# STEPPER.net
KiCad netlist of a schematic drawn in Altium Designer
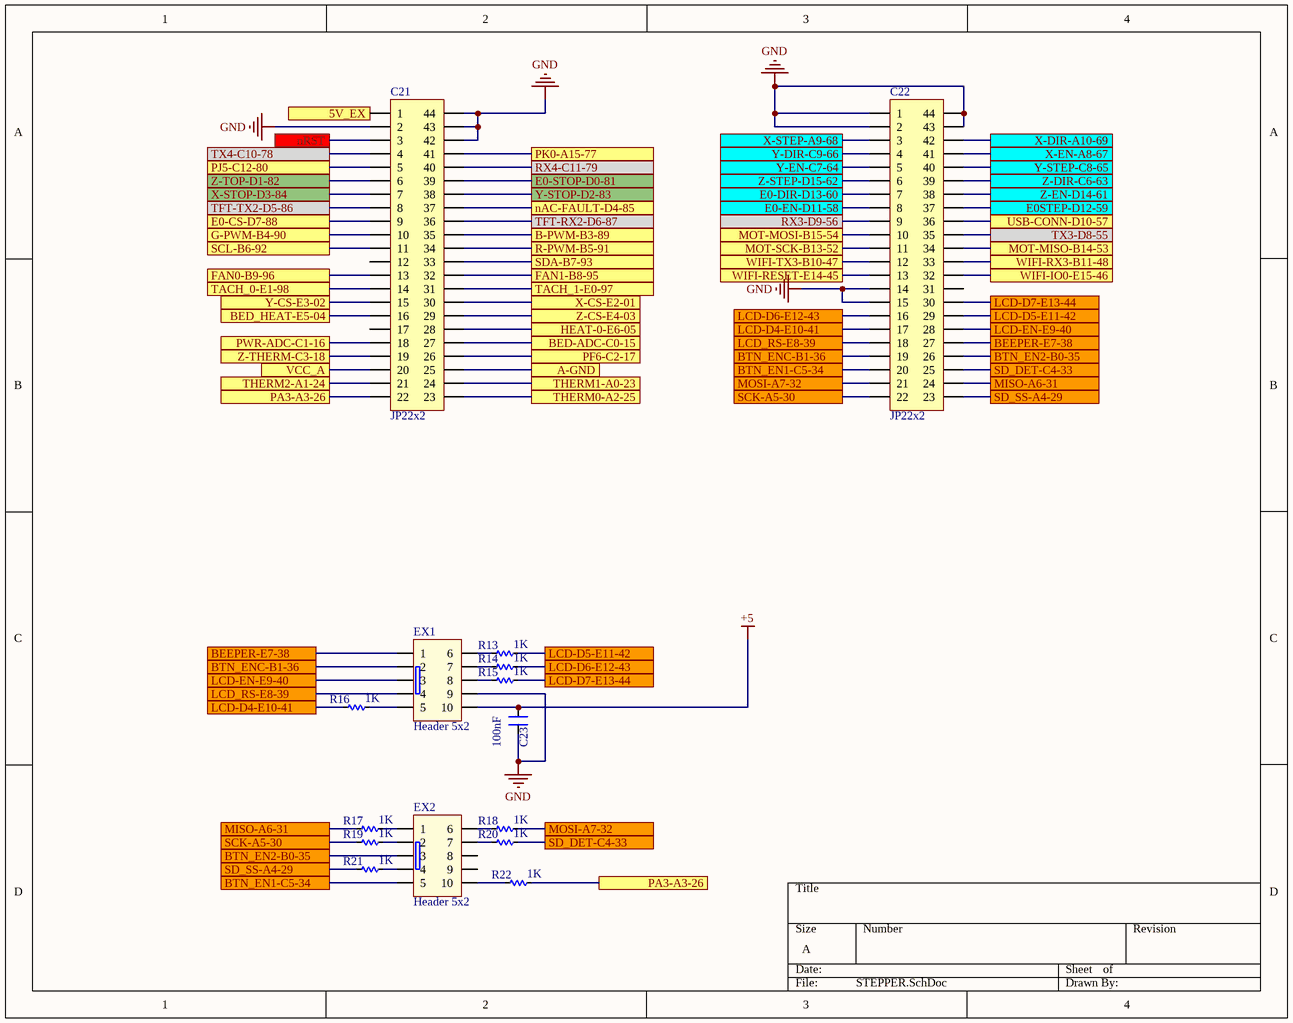
[diagram p0: STEPPER.SchDoc]

(export (version "E")
  (design (tool "Eeschema 10.0.6"))
  (components
    (comp (ref "C21")
      (value "JP22x2")
      (footprint "JP22-C2T")
      (description "WR-PHD 2.54 mm Dual Socket Header")
      (fields
        (field (name "MANUFACTURER") "Würth Elektronik eiSos GmbH")
        (field (name "PARTNO") "61304421821")
        (field (name "CREATED BY") "Karrer Zheng")
      )
      (libsource (lib "nhan") (part "JP22x2"))
    )
    (comp (ref "C22")
      (value "JP22x2")
      (footprint "JP22-C2T")
      (description "WR-PHD 2.54 mm Dual Socket Header")
      (fields
        (field (name "MANUFACTURER") "Würth Elektronik eiSos GmbH")
        (field (name "PARTNO") "61304421821")
        (field (name "CREATED BY") "Karrer Zheng")
      )
      (libsource (lib "nhan") (part "JP22x2"))
    )
    (comp (ref "C23") (value "100nF") (footprint "CN-SMD-0603_big") (libsource (lib "nhan") (part "CN")))
    (comp (ref "EX1")
      (value "Header 5x2")
      (footprint "Hed2X5")
      (libsource (lib "syhaunguyen") (part "HED5x2"))
    )
    (comp (ref "EX2")
      (value "Header 5x2")
      (footprint "Hed2X5")
      (libsource (lib "syhaunguyen") (part "HED5x2"))
    )
    (comp (ref "R13") (value "1K") (footprint "RES-SMD-0603_BIG") (libsource (lib "nhan") (part "R")))
    (comp (ref "R14") (value "1K") (footprint "RES-SMD-0603_BIG") (libsource (lib "nhan") (part "R")))
    (comp (ref "R15") (value "1K") (footprint "RES-SMD-0603_BIG") (libsource (lib "nhan") (part "R")))
    (comp (ref "R16") (value "1K") (footprint "RES-SMD-0603_BIG") (libsource (lib "nhan") (part "R")))
    (comp (ref "R17") (value "1K") (footprint "RES-SMD-0603_BIG") (libsource (lib "nhan") (part "R")))
    (comp (ref "R18") (value "1K") (footprint "RES-SMD-0603_BIG") (libsource (lib "nhan") (part "R")))
    (comp (ref "R19") (value "1K") (footprint "RES-SMD-0603_BIG") (libsource (lib "nhan") (part "R")))
    (comp (ref "R20") (value "1K") (footprint "RES-SMD-0603_BIG") (libsource (lib "nhan") (part "R")))
    (comp (ref "R21") (value "1K") (footprint "RES-SMD-0603_BIG") (libsource (lib "nhan") (part "R")))
    (comp (ref "R22") (value "1K") (footprint "RES-SMD-0603_BIG") (libsource (lib "nhan") (part "R")))
  )
  (nets
    (net (code "1") (name "+5") (class "Default")
      (node (ref "C23") (pin "2") (pinfunction "2_2") (pintype "passive"))
      (node (ref "EX1") (pin "10") (pinfunction "10_10") (pintype "passive"))
    )
    (net (code "2") (name "/5V_EX") (class "Default")
      (node (ref "C21") (pin "1") (pinfunction "1_1") (pintype "passive"))
    )
    (net (code "3") (name "/A-GND") (class "Default")
      (node (ref "C21") (pin "25") (pinfunction "25_25") (pintype "passive"))
    )
    (net (code "4") (name "/B-PWM-B3-89") (class "Default")
      (node (ref "C21") (pin "35") (pinfunction "35_35") (pintype "passive"))
    )
    (net (code "5") (name "/BED-ADC-C0-15") (class "Default")
      (node (ref "C21") (pin "27") (pinfunction "27_27") (pintype "passive"))
    )
    (net (code "6") (name "/BED_HEAT-E5-04") (class "Default")
      (node (ref "C21") (pin "16") (pinfunction "16_16") (pintype "passive"))
    )
    (net (code "7") (name "/BEEPER-E7-38") (class "Default")
      (node (ref "C22") (pin "27") (pinfunction "27_27") (pintype "passive"))
      (node (ref "EX1") (pin "1") (pinfunction "1_1") (pintype "passive"))
    )
    (net (code "8") (name "/BTN_EN1-C5-34") (class "Default")
      (node (ref "C22") (pin "20") (pinfunction "20_20") (pintype "passive"))
      (node (ref "EX2") (pin "5") (pinfunction "5_5") (pintype "passive"))
    )
    (net (code "9") (name "/BTN_EN2-B0-35") (class "Default")
      (node (ref "C22") (pin "26") (pinfunction "26_26") (pintype "passive"))
      (node (ref "EX2") (pin "3") (pinfunction "3_3") (pintype "passive"))
    )
    (net (code "10") (name "/BTN_ENC-B1-36") (class "Default")
      (node (ref "C22") (pin "19") (pinfunction "19_19") (pintype "passive"))
      (node (ref "EX1") (pin "2") (pinfunction "2_2") (pintype "passive"))
    )
    (net (code "11") (name "/E0-CS-D7-88") (class "Default")
      (node (ref "C21") (pin "9") (pinfunction "9_9") (pintype "passive"))
    )
    (net (code "12") (name "/E0-DIR-D13-60") (class "Default")
      (node (ref "C22") (pin "7") (pinfunction "7_7") (pintype "passive"))
    )
    (net (code "13") (name "/E0-EN-D11-58") (class "Default")
      (node (ref "C22") (pin "8") (pinfunction "8_8") (pintype "passive"))
    )
    (net (code "14") (name "/E0-STOP-D0-81") (class "Default")
      (node (ref "C21") (pin "39") (pinfunction "39_39") (pintype "passive"))
    )
    (net (code "15") (name "/E0STEP-D12-59") (class "Default")
      (node (ref "C22") (pin "37") (pinfunction "37_37") (pintype "passive"))
    )
    (net (code "16") (name "/FAN0-B9-96") (class "Default")
      (node (ref "C21") (pin "13") (pinfunction "13_13") (pintype "passive"))
    )
    (net (code "17") (name "/FAN1-B8-95") (class "Default")
      (node (ref "C21") (pin "32") (pinfunction "32_32") (pintype "passive"))
    )
    (net (code "18") (name "/G-PWM-B4-90") (class "Default")
      (node (ref "C21") (pin "10") (pinfunction "10_10") (pintype "passive"))
    )
    (net (code "19") (name "/HEAT-0-E6-05") (class "Default")
      (node (ref "C21") (pin "28") (pinfunction "28_28") (pintype "passive"))
    )
    (net (code "20") (name "/LCD-D4-E10-41") (class "Default")
      (node (ref "C22") (pin "17") (pinfunction "17_17") (pintype "passive"))
      (node (ref "R16") (pin "2") (pinfunction "2_2") (pintype "passive"))
    )
    (net (code "21") (name "/LCD-D5-E11-42") (class "Default")
      (node (ref "C22") (pin "29") (pinfunction "29_29") (pintype "passive"))
      (node (ref "R13") (pin "1") (pinfunction "1_1") (pintype "passive"))
    )
    (net (code "22") (name "/LCD-D6-E12-43") (class "Default")
      (node (ref "C22") (pin "16") (pinfunction "16_16") (pintype "passive"))
      (node (ref "R14") (pin "1") (pinfunction "1_1") (pintype "passive"))
    )
    (net (code "23") (name "/LCD-D7-E13-44") (class "Default")
      (node (ref "C22") (pin "30") (pinfunction "30_30") (pintype "passive"))
      (node (ref "R15") (pin "1") (pinfunction "1_1") (pintype "passive"))
    )
    (net (code "24") (name "/LCD-EN-E9-40") (class "Default")
      (node (ref "C22") (pin "28") (pinfunction "28_28") (pintype "passive"))
      (node (ref "EX1") (pin "3") (pinfunction "3_3") (pintype "passive"))
    )
    (net (code "25") (name "/LCD_RS-E8-39") (class "Default")
      (node (ref "C22") (pin "18") (pinfunction "18_18") (pintype "passive"))
      (node (ref "EX1") (pin "4") (pinfunction "4_4") (pintype "passive"))
    )
    (net (code "26") (name "/MISO-A6-31") (class "Default")
      (node (ref "C22") (pin "24") (pinfunction "24_24") (pintype "passive"))
      (node (ref "R17") (pin "2") (pinfunction "2_2") (pintype "passive"))
    )
    (net (code "27") (name "/MOSI-A7-32") (class "Default")
      (node (ref "C22") (pin "21") (pinfunction "21_21") (pintype "passive"))
      (node (ref "R18") (pin "1") (pinfunction "1_1") (pintype "passive"))
    )
    (net (code "28") (name "/MOT-MISO-B14-53") (class "Default")
      (node (ref "C22") (pin "34") (pinfunction "34_34") (pintype "passive"))
    )
    (net (code "29") (name "/MOT-MOSI-B15-54") (class "Default")
      (node (ref "C22") (pin "10") (pinfunction "10_10") (pintype "passive"))
    )
    (net (code "30") (name "/MOT-SCK-B13-52") (class "Default")
      (node (ref "C22") (pin "11") (pinfunction "11_11") (pintype "passive"))
    )
    (net (code "31") (name "/PA3-A3-26") (class "Default")
      (node (ref "C21") (pin "22") (pinfunction "22_22") (pintype "passive"))
      (node (ref "R22") (pin "1") (pinfunction "1_1") (pintype "passive"))
    )
    (net (code "32") (name "/PF6-C2-17") (class "Default")
      (node (ref "C21") (pin "26") (pinfunction "26_26") (pintype "passive"))
    )
    (net (code "33") (name "/PJ5-C12-80") (class "Default")
      (node (ref "C21") (pin "5") (pinfunction "5_5") (pintype "passive"))
    )
    (net (code "34") (name "/PK0-A15-77") (class "Default")
      (node (ref "C21") (pin "41") (pinfunction "41_41") (pintype "passive"))
    )
    (net (code "35") (name "/PWR-ADC-C1-16") (class "Default")
      (node (ref "C21") (pin "18") (pinfunction "18_18") (pintype "passive"))
    )
    (net (code "36") (name "/R-PWM-B5-91") (class "Default")
      (node (ref "C21") (pin "34") (pinfunction "34_34") (pintype "passive"))
    )
    (net (code "37") (name "/RX3-D9-56") (class "Default")
      (node (ref "C22") (pin "9") (pinfunction "9_9") (pintype "passive"))
    )
    (net (code "38") (name "/RX4-C11-79") (class "Default")
      (node (ref "C21") (pin "40") (pinfunction "40_40") (pintype "passive"))
    )
    (net (code "39") (name "/SCK-A5-30") (class "Default")
      (node (ref "C22") (pin "22") (pinfunction "22_22") (pintype "passive"))
      (node (ref "R19") (pin "2") (pinfunction "2_2") (pintype "passive"))
    )
    (net (code "40") (name "/SCL-B6-92") (class "Default")
      (node (ref "C21") (pin "11") (pinfunction "11_11") (pintype "passive"))
    )
    (net (code "41") (name "/SDA-B7-93") (class "Default")
      (node (ref "C21") (pin "33") (pinfunction "33_33") (pintype "passive"))
    )
    (net (code "42") (name "/SD_DET-C4-33") (class "Default")
      (node (ref "C22") (pin "25") (pinfunction "25_25") (pintype "passive"))
      (node (ref "R20") (pin "1") (pinfunction "1_1") (pintype "passive"))
    )
    (net (code "43") (name "/SD_SS-A4-29") (class "Default")
      (node (ref "C22") (pin "23") (pinfunction "23_23") (pintype "passive"))
      (node (ref "R21") (pin "2") (pinfunction "2_2") (pintype "passive"))
    )
    (net (code "44") (name "/TACH_0-E1-98") (class "Default")
      (node (ref "C21") (pin "14") (pinfunction "14_14") (pintype "passive"))
    )
    (net (code "45") (name "/TACH_1-E0-97") (class "Default")
      (node (ref "C21") (pin "31") (pinfunction "31_31") (pintype "passive"))
    )
    (net (code "46") (name "/TFT-RX2-D6-87") (class "Default")
      (node (ref "C21") (pin "36") (pinfunction "36_36") (pintype "passive"))
    )
    (net (code "47") (name "/TFT-TX2-D5-86") (class "Default")
      (node (ref "C21") (pin "8") (pinfunction "8_8") (pintype "passive"))
    )
    (net (code "48") (name "/THERM0-A2-25") (class "Default")
      (node (ref "C21") (pin "23") (pinfunction "23_23") (pintype "passive"))
    )
    (net (code "49") (name "/THERM1-A0-23") (class "Default")
      (node (ref "C21") (pin "24") (pinfunction "24_24") (pintype "passive"))
    )
    (net (code "50") (name "/THERM2-A1-24") (class "Default")
      (node (ref "C21") (pin "21") (pinfunction "21_21") (pintype "passive"))
    )
    (net (code "51") (name "/TX3-D8-55") (class "Default")
      (node (ref "C22") (pin "35") (pinfunction "35_35") (pintype "passive"))
    )
    (net (code "52") (name "/TX4-C10-78") (class "Default")
      (node (ref "C21") (pin "4") (pinfunction "4_4") (pintype "passive"))
    )
    (net (code "53") (name "/USB-CONN-D10-57") (class "Default")
      (node (ref "C22") (pin "36") (pinfunction "36_36") (pintype "passive"))
    )
    (net (code "54") (name "/VCC_A") (class "Default")
      (node (ref "C21") (pin "20") (pinfunction "20_20") (pintype "passive"))
    )
    (net (code "55") (name "/WIFI-IO0-E15-46") (class "Default")
      (node (ref "C22") (pin "32") (pinfunction "32_32") (pintype "passive"))
    )
    (net (code "56") (name "/WIFI-RESET-E14-45") (class "Default")
      (node (ref "C22") (pin "13") (pinfunction "13_13") (pintype "passive"))
    )
    (net (code "57") (name "/WIFI-RX3-B11-48") (class "Default")
      (node (ref "C22") (pin "33") (pinfunction "33_33") (pintype "passive"))
    )
    (net (code "58") (name "/WIFI-TX3-B10-47") (class "Default")
      (node (ref "C22") (pin "12") (pinfunction "12_12") (pintype "passive"))
    )
    (net (code "59") (name "/X-CS-E2-01") (class "Default")
      (node (ref "C21") (pin "30") (pinfunction "30_30") (pintype "passive"))
    )
    (net (code "60") (name "/X-DIR-A10-69") (class "Default")
      (node (ref "C22") (pin "42") (pinfunction "42_42") (pintype "passive"))
    )
    (net (code "61") (name "/X-EN-A8-67") (class "Default")
      (node (ref "C22") (pin "41") (pinfunction "41_41") (pintype "passive"))
    )
    (net (code "62") (name "/X-STEP-A9-68") (class "Default")
      (node (ref "C22") (pin "3") (pinfunction "3_3") (pintype "passive"))
    )
    (net (code "63") (name "/X-STOP-D3-84") (class "Default")
      (node (ref "C21") (pin "7") (pinfunction "7_7") (pintype "passive"))
    )
    (net (code "64") (name "/Y-CS-E3-02") (class "Default")
      (node (ref "C21") (pin "15") (pinfunction "15_15") (pintype "passive"))
    )
    (net (code "65") (name "/Y-DIR-C9-66") (class "Default")
      (node (ref "C22") (pin "4") (pinfunction "4_4") (pintype "passive"))
    )
    (net (code "66") (name "/Y-EN-C7-64") (class "Default")
      (node (ref "C22") (pin "5") (pinfunction "5_5") (pintype "passive"))
    )
    (net (code "67") (name "/Y-STEP-C8-65") (class "Default")
      (node (ref "C22") (pin "40") (pinfunction "40_40") (pintype "passive"))
    )
    (net (code "68") (name "/Y-STOP-D2-83") (class "Default")
      (node (ref "C21") (pin "38") (pinfunction "38_38") (pintype "passive"))
    )
    (net (code "69") (name "/Z-CS-E4-03") (class "Default")
      (node (ref "C21") (pin "29") (pinfunction "29_29") (pintype "passive"))
    )
    (net (code "70") (name "/Z-DIR-C6-63") (class "Default")
      (node (ref "C22") (pin "39") (pinfunction "39_39") (pintype "passive"))
    )
    (net (code "71") (name "/Z-EN-D14-61") (class "Default")
      (node (ref "C22") (pin "38") (pinfunction "38_38") (pintype "passive"))
    )
    (net (code "72") (name "/Z-STEP-D15-62") (class "Default")
      (node (ref "C22") (pin "6") (pinfunction "6_6") (pintype "passive"))
    )
    (net (code "73") (name "/Z-THERM-C3-18") (class "Default")
      (node (ref "C21") (pin "19") (pinfunction "19_19") (pintype "passive"))
    )
    (net (code "74") (name "/Z-TOP-D1-82") (class "Default")
      (node (ref "C21") (pin "6") (pinfunction "6_6") (pintype "passive"))
    )
    (net (code "75") (name "/nAC-FAULT-D4-85") (class "Default")
      (node (ref "C21") (pin "37") (pinfunction "37_37") (pintype "passive"))
    )
    (net (code "76") (name "/nRST") (class "Default")
      (node (ref "C21") (pin "3") (pinfunction "3_3") (pintype "passive"))
    )
    (net (code "77") (name "GND") (class "Default")
      (node (ref "C21") (pin "2") (pinfunction "2_2") (pintype "passive"))
      (node (ref "C21") (pin "42") (pinfunction "42_42") (pintype "passive"))
      (node (ref "C21") (pin "43") (pinfunction "43_43") (pintype "passive"))
      (node (ref "C21") (pin "44") (pinfunction "44_44") (pintype "passive"))
      (node (ref "C22") (pin "1") (pinfunction "1_1") (pintype "passive"))
      (node (ref "C22") (pin "14") (pinfunction "14_14") (pintype "passive"))
      (node (ref "C22") (pin "15") (pinfunction "15_15") (pintype "passive"))
      (node (ref "C22") (pin "2") (pinfunction "2_2") (pintype "passive"))
      (node (ref "C22") (pin "43") (pinfunction "43_43") (pintype "passive"))
      (node (ref "C22") (pin "44") (pinfunction "44_44") (pintype "passive"))
      (node (ref "C23") (pin "1") (pinfunction "1_1") (pintype "passive"))
      (node (ref "EX1") (pin "9") (pinfunction "9_9") (pintype "passive"))
    )
    (net (code "78") (name "Net-(EX1-Pad5)") (class "Default")
      (node (ref "EX1") (pin "5") (pinfunction "5_5") (pintype "passive"))
      (node (ref "R16") (pin "1") (pinfunction "1_1") (pintype "passive"))
    )
    (net (code "79") (name "Net-(EX1-Pad6)") (class "Default")
      (node (ref "EX1") (pin "6") (pinfunction "6_6") (pintype "passive"))
      (node (ref "R13") (pin "2") (pinfunction "2_2") (pintype "passive"))
    )
    (net (code "80") (name "Net-(EX1-Pad7)") (class "Default")
      (node (ref "EX1") (pin "7") (pinfunction "7_7") (pintype "passive"))
      (node (ref "R14") (pin "2") (pinfunction "2_2") (pintype "passive"))
    )
    (net (code "81") (name "Net-(EX1-Pad8)") (class "Default")
      (node (ref "EX1") (pin "8") (pinfunction "8_8") (pintype "passive"))
      (node (ref "R15") (pin "2") (pinfunction "2_2") (pintype "passive"))
    )
    (net (code "82") (name "Net-(EX2-Pad1)") (class "Default")
      (node (ref "EX2") (pin "1") (pinfunction "1_1") (pintype "passive"))
      (node (ref "R17") (pin "1") (pinfunction "1_1") (pintype "passive"))
    )
    (net (code "83") (name "Net-(EX2-Pad2)") (class "Default")
      (node (ref "EX2") (pin "2") (pinfunction "2_2") (pintype "passive"))
      (node (ref "R19") (pin "1") (pinfunction "1_1") (pintype "passive"))
    )
    (net (code "84") (name "Net-(EX2-Pad4)") (class "Default")
      (node (ref "EX2") (pin "4") (pinfunction "4_4") (pintype "passive"))
      (node (ref "R21") (pin "1") (pinfunction "1_1") (pintype "passive"))
    )
    (net (code "85") (name "Net-(EX2-Pad6)") (class "Default")
      (node (ref "EX2") (pin "6") (pinfunction "6_6") (pintype "passive"))
      (node (ref "R18") (pin "2") (pinfunction "2_2") (pintype "passive"))
    )
    (net (code "86") (name "Net-(EX2-Pad7)") (class "Default")
      (node (ref "EX2") (pin "7") (pinfunction "7_7") (pintype "passive"))
      (node (ref "R20") (pin "2") (pinfunction "2_2") (pintype "passive"))
    )
    (net (code "87") (name "Net-(EX2-Pad10)") (class "Default")
      (node (ref "EX2") (pin "10") (pinfunction "10_10") (pintype "passive"))
      (node (ref "R22") (pin "2") (pinfunction "2_2") (pintype "passive"))
    )
    (net (code "88") (name "unconnected-(C21-Pad12)") (class "Default")
      (node (ref "C21") (pin "12") (pinfunction "12_12") (pintype "passive"))
    )
    (net (code "89") (name "unconnected-(C21-Pad17)") (class "Default")
      (node (ref "C21") (pin "17") (pinfunction "17_17") (pintype "passive"))
    )
    (net (code "90") (name "unconnected-(C22-Pad31)") (class "Default")
      (node (ref "C22") (pin "31") (pinfunction "31_31") (pintype "passive"))
    )
    (net (code "91") (name "unconnected-(EX2-Pad8)") (class "Default")
      (node (ref "EX2") (pin "8") (pinfunction "8_8") (pintype "passive"))
    )
    (net (code "92") (name "unconnected-(EX2-Pad9)") (class "Default")
      (node (ref "EX2") (pin "9") (pinfunction "9_9") (pintype "passive"))
    )
  )
)
